# input.net
KiCad netlist of a schematic drawn in EAGLE
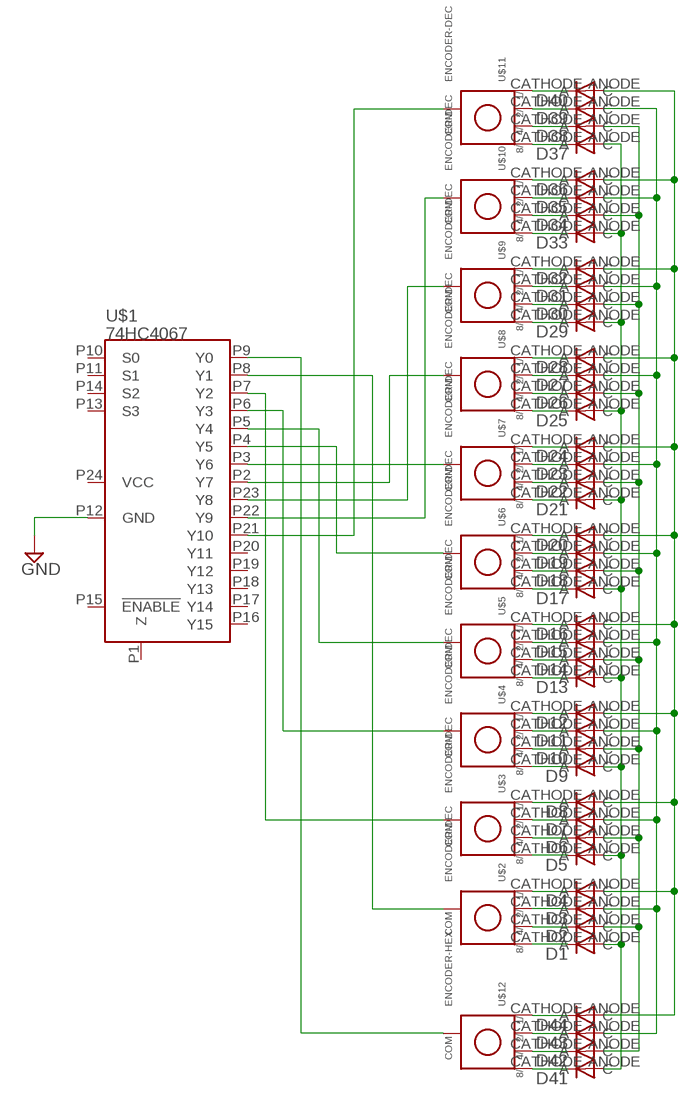
[diagram p0: schematic, sheet 1]

(export (version "E")
  (design (tool "Eeschema 10.0.6"))
  (components
    (comp (ref "D1")
      (value "TS4148")
      (footprint "eagle-import:0805")
      (libsource (lib "eagle-import") (part "TS4148"))
    )
    (comp (ref "D2")
      (value "TS4148")
      (footprint "eagle-import:0805")
      (libsource (lib "eagle-import") (part "TS4148"))
    )
    (comp (ref "D3")
      (value "TS4148")
      (footprint "eagle-import:0805")
      (libsource (lib "eagle-import") (part "TS4148"))
    )
    (comp (ref "D4")
      (value "TS4148")
      (footprint "eagle-import:0805")
      (libsource (lib "eagle-import") (part "TS4148"))
    )
    (comp (ref "D5")
      (value "TS4148")
      (footprint "eagle-import:0805")
      (libsource (lib "eagle-import") (part "TS4148"))
    )
    (comp (ref "D6")
      (value "TS4148")
      (footprint "eagle-import:0805")
      (libsource (lib "eagle-import") (part "TS4148"))
    )
    (comp (ref "D7")
      (value "TS4148")
      (footprint "eagle-import:0805")
      (libsource (lib "eagle-import") (part "TS4148"))
    )
    (comp (ref "D8")
      (value "TS4148")
      (footprint "eagle-import:0805")
      (libsource (lib "eagle-import") (part "TS4148"))
    )
    (comp (ref "D9")
      (value "TS4148")
      (footprint "eagle-import:0805")
      (libsource (lib "eagle-import") (part "TS4148"))
    )
    (comp (ref "D10")
      (value "TS4148")
      (footprint "eagle-import:0805")
      (libsource (lib "eagle-import") (part "TS4148"))
    )
    (comp (ref "D11")
      (value "TS4148")
      (footprint "eagle-import:0805")
      (libsource (lib "eagle-import") (part "TS4148"))
    )
    (comp (ref "D12")
      (value "TS4148")
      (footprint "eagle-import:0805")
      (libsource (lib "eagle-import") (part "TS4148"))
    )
    (comp (ref "D13")
      (value "TS4148")
      (footprint "eagle-import:0805")
      (libsource (lib "eagle-import") (part "TS4148"))
    )
    (comp (ref "D14")
      (value "TS4148")
      (footprint "eagle-import:0805")
      (libsource (lib "eagle-import") (part "TS4148"))
    )
    (comp (ref "D15")
      (value "TS4148")
      (footprint "eagle-import:0805")
      (libsource (lib "eagle-import") (part "TS4148"))
    )
    (comp (ref "D16")
      (value "TS4148")
      (footprint "eagle-import:0805")
      (libsource (lib "eagle-import") (part "TS4148"))
    )
    (comp (ref "D17")
      (value "TS4148")
      (footprint "eagle-import:0805")
      (libsource (lib "eagle-import") (part "TS4148"))
    )
    (comp (ref "D18")
      (value "TS4148")
      (footprint "eagle-import:0805")
      (libsource (lib "eagle-import") (part "TS4148"))
    )
    (comp (ref "D19")
      (value "TS4148")
      (footprint "eagle-import:0805")
      (libsource (lib "eagle-import") (part "TS4148"))
    )
    (comp (ref "D20")
      (value "TS4148")
      (footprint "eagle-import:0805")
      (libsource (lib "eagle-import") (part "TS4148"))
    )
    (comp (ref "D21")
      (value "TS4148")
      (footprint "eagle-import:0805")
      (libsource (lib "eagle-import") (part "TS4148"))
    )
    (comp (ref "D22")
      (value "TS4148")
      (footprint "eagle-import:0805")
      (libsource (lib "eagle-import") (part "TS4148"))
    )
    (comp (ref "D23")
      (value "TS4148")
      (footprint "eagle-import:0805")
      (libsource (lib "eagle-import") (part "TS4148"))
    )
    (comp (ref "D24")
      (value "TS4148")
      (footprint "eagle-import:0805")
      (libsource (lib "eagle-import") (part "TS4148"))
    )
    (comp (ref "D25")
      (value "TS4148")
      (footprint "eagle-import:0805")
      (libsource (lib "eagle-import") (part "TS4148"))
    )
    (comp (ref "D26")
      (value "TS4148")
      (footprint "eagle-import:0805")
      (libsource (lib "eagle-import") (part "TS4148"))
    )
    (comp (ref "D27")
      (value "TS4148")
      (footprint "eagle-import:0805")
      (libsource (lib "eagle-import") (part "TS4148"))
    )
    (comp (ref "D28")
      (value "TS4148")
      (footprint "eagle-import:0805")
      (libsource (lib "eagle-import") (part "TS4148"))
    )
    (comp (ref "D29")
      (value "TS4148")
      (footprint "eagle-import:0805")
      (libsource (lib "eagle-import") (part "TS4148"))
    )
    (comp (ref "D30")
      (value "TS4148")
      (footprint "eagle-import:0805")
      (libsource (lib "eagle-import") (part "TS4148"))
    )
    (comp (ref "D31")
      (value "TS4148")
      (footprint "eagle-import:0805")
      (libsource (lib "eagle-import") (part "TS4148"))
    )
    (comp (ref "D32")
      (value "TS4148")
      (footprint "eagle-import:0805")
      (libsource (lib "eagle-import") (part "TS4148"))
    )
    (comp (ref "D33")
      (value "TS4148")
      (footprint "eagle-import:0805")
      (libsource (lib "eagle-import") (part "TS4148"))
    )
    (comp (ref "D34")
      (value "TS4148")
      (footprint "eagle-import:0805")
      (libsource (lib "eagle-import") (part "TS4148"))
    )
    (comp (ref "D35")
      (value "TS4148")
      (footprint "eagle-import:0805")
      (libsource (lib "eagle-import") (part "TS4148"))
    )
    (comp (ref "D36")
      (value "TS4148")
      (footprint "eagle-import:0805")
      (libsource (lib "eagle-import") (part "TS4148"))
    )
    (comp (ref "D37")
      (value "TS4148")
      (footprint "eagle-import:0805")
      (libsource (lib "eagle-import") (part "TS4148"))
    )
    (comp (ref "D38")
      (value "TS4148")
      (footprint "eagle-import:0805")
      (libsource (lib "eagle-import") (part "TS4148"))
    )
    (comp (ref "D39")
      (value "TS4148")
      (footprint "eagle-import:0805")
      (libsource (lib "eagle-import") (part "TS4148"))
    )
    (comp (ref "D40")
      (value "TS4148")
      (footprint "eagle-import:0805")
      (libsource (lib "eagle-import") (part "TS4148"))
    )
    (comp (ref "D41")
      (value "TS4148")
      (footprint "eagle-import:0805")
      (libsource (lib "eagle-import") (part "TS4148"))
    )
    (comp (ref "D42")
      (value "TS4148")
      (footprint "eagle-import:0805")
      (libsource (lib "eagle-import") (part "TS4148"))
    )
    (comp (ref "D43")
      (value "TS4148")
      (footprint "eagle-import:0805")
      (libsource (lib "eagle-import") (part "TS4148"))
    )
    (comp (ref "D44")
      (value "TS4148")
      (footprint "eagle-import:0805")
      (libsource (lib "eagle-import") (part "TS4148"))
    )
    (comp (ref "U$1")
      (value "74HC4067")
      (footprint "eagle-import:DIP-24")
      (libsource (lib "eagle-import") (part "74HC4067"))
    )
    (comp (ref "U$2")
      (value "ENCODER-DEC")
      (footprint "eagle-import:4-BIT-ENCODER")
      (libsource (lib "eagle-import") (part "ENCODER-DEC"))
    )
    (comp (ref "U$3")
      (value "ENCODER-DEC")
      (footprint "eagle-import:4-BIT-ENCODER")
      (libsource (lib "eagle-import") (part "ENCODER-DEC"))
    )
    (comp (ref "U$4")
      (value "ENCODER-DEC")
      (footprint "eagle-import:4-BIT-ENCODER")
      (libsource (lib "eagle-import") (part "ENCODER-DEC"))
    )
    (comp (ref "U$5")
      (value "ENCODER-DEC")
      (footprint "eagle-import:4-BIT-ENCODER")
      (libsource (lib "eagle-import") (part "ENCODER-DEC"))
    )
    (comp (ref "U$6")
      (value "ENCODER-DEC")
      (footprint "eagle-import:4-BIT-ENCODER")
      (libsource (lib "eagle-import") (part "ENCODER-DEC"))
    )
    (comp (ref "U$7")
      (value "ENCODER-DEC")
      (footprint "eagle-import:4-BIT-ENCODER")
      (libsource (lib "eagle-import") (part "ENCODER-DEC"))
    )
    (comp (ref "U$8")
      (value "ENCODER-DEC")
      (footprint "eagle-import:4-BIT-ENCODER")
      (libsource (lib "eagle-import") (part "ENCODER-DEC"))
    )
    (comp (ref "U$9")
      (value "ENCODER-DEC")
      (footprint "eagle-import:4-BIT-ENCODER")
      (libsource (lib "eagle-import") (part "ENCODER-DEC"))
    )
    (comp (ref "U$10")
      (value "ENCODER-DEC")
      (footprint "eagle-import:4-BIT-ENCODER")
      (libsource (lib "eagle-import") (part "ENCODER-DEC"))
    )
    (comp (ref "U$11")
      (value "ENCODER-DEC")
      (footprint "eagle-import:4-BIT-ENCODER")
      (libsource (lib "eagle-import") (part "ENCODER-DEC"))
    )
    (comp (ref "U$12")
      (value "ENCODER-HEX")
      (footprint "eagle-import:4-BIT-ENCODER")
      (libsource (lib "eagle-import") (part "ENCODER-HEX"))
    )
  )
  (nets
    (net (code "1") (name "/VCC") (class "Default")
      (node (ref "U$1") (pin "P24") (pinfunction "VCC_P24") (pintype "power_in"))
    )
    (net (code "2") (name "GND") (class "Default")
      (node (ref "U$1") (pin "P12") (pinfunction "GND_P12") (pintype "power_in"))
    )
    (net (code "3") (name "Net-(D1-A)") (class "Default")
      (node (ref "D1") (pin "ANODE") (pinfunction "A_ANODE") (pintype "bidirectional"))
      (node (ref "D13") (pin "ANODE") (pinfunction "A_ANODE") (pintype "bidirectional"))
      (node (ref "D17") (pin "ANODE") (pinfunction "A_ANODE") (pintype "bidirectional"))
      (node (ref "D21") (pin "ANODE") (pinfunction "A_ANODE") (pintype "bidirectional"))
      (node (ref "D25") (pin "ANODE") (pinfunction "A_ANODE") (pintype "bidirectional"))
      (node (ref "D29") (pin "ANODE") (pinfunction "A_ANODE") (pintype "bidirectional"))
      (node (ref "D33") (pin "ANODE") (pinfunction "A_ANODE") (pintype "bidirectional"))
      (node (ref "D37") (pin "ANODE") (pinfunction "A_ANODE") (pintype "bidirectional"))
      (node (ref "D41") (pin "ANODE") (pinfunction "A_ANODE") (pintype "bidirectional"))
      (node (ref "D5") (pin "ANODE") (pinfunction "A_ANODE") (pintype "bidirectional"))
      (node (ref "D9") (pin "ANODE") (pinfunction "A_ANODE") (pintype "bidirectional"))
    )
    (net (code "4") (name "Net-(D1-C)") (class "Default")
      (node (ref "D1") (pin "CATHODE") (pinfunction "C_CATHODE") (pintype "bidirectional"))
      (node (ref "U$2") (pin "8/") (pinfunction "8/_8/") (pintype "bidirectional"))
    )
    (net (code "5") (name "Net-(D2-C)") (class "Default")
      (node (ref "D2") (pin "CATHODE") (pinfunction "C_CATHODE") (pintype "bidirectional"))
      (node (ref "U$2") (pin "4/") (pinfunction "4/_4/") (pintype "bidirectional"))
    )
    (net (code "6") (name "Net-(D3-C)") (class "Default")
      (node (ref "D3") (pin "CATHODE") (pinfunction "C_CATHODE") (pintype "bidirectional"))
      (node (ref "U$2") (pin "2/") (pinfunction "2/_2/") (pintype "bidirectional"))
    )
    (net (code "7") (name "Net-(D4-C)") (class "Default")
      (node (ref "D4") (pin "CATHODE") (pinfunction "C_CATHODE") (pintype "bidirectional"))
      (node (ref "U$2") (pin "1/") (pinfunction "1/_1/") (pintype "bidirectional"))
    )
    (net (code "8") (name "Net-(D5-C)") (class "Default")
      (node (ref "D5") (pin "CATHODE") (pinfunction "C_CATHODE") (pintype "bidirectional"))
      (node (ref "U$3") (pin "8/") (pinfunction "8/_8/") (pintype "bidirectional"))
    )
    (net (code "9") (name "Net-(D6-C)") (class "Default")
      (node (ref "D6") (pin "CATHODE") (pinfunction "C_CATHODE") (pintype "bidirectional"))
      (node (ref "U$3") (pin "4/") (pinfunction "4/_4/") (pintype "bidirectional"))
    )
    (net (code "10") (name "Net-(D7-C)") (class "Default")
      (node (ref "D7") (pin "CATHODE") (pinfunction "C_CATHODE") (pintype "bidirectional"))
      (node (ref "U$3") (pin "2/") (pinfunction "2/_2/") (pintype "bidirectional"))
    )
    (net (code "11") (name "Net-(D8-C)") (class "Default")
      (node (ref "D8") (pin "CATHODE") (pinfunction "C_CATHODE") (pintype "bidirectional"))
      (node (ref "U$3") (pin "1/") (pinfunction "1/_1/") (pintype "bidirectional"))
    )
    (net (code "12") (name "Net-(D9-C)") (class "Default")
      (node (ref "D9") (pin "CATHODE") (pinfunction "C_CATHODE") (pintype "bidirectional"))
      (node (ref "U$4") (pin "8/") (pinfunction "8/_8/") (pintype "bidirectional"))
    )
    (net (code "13") (name "Net-(D10-A)") (class "Default")
      (node (ref "D10") (pin "ANODE") (pinfunction "A_ANODE") (pintype "bidirectional"))
      (node (ref "D14") (pin "ANODE") (pinfunction "A_ANODE") (pintype "bidirectional"))
      (node (ref "D18") (pin "ANODE") (pinfunction "A_ANODE") (pintype "bidirectional"))
      (node (ref "D2") (pin "ANODE") (pinfunction "A_ANODE") (pintype "bidirectional"))
      (node (ref "D22") (pin "ANODE") (pinfunction "A_ANODE") (pintype "bidirectional"))
      (node (ref "D26") (pin "ANODE") (pinfunction "A_ANODE") (pintype "bidirectional"))
      (node (ref "D30") (pin "ANODE") (pinfunction "A_ANODE") (pintype "bidirectional"))
      (node (ref "D34") (pin "ANODE") (pinfunction "A_ANODE") (pintype "bidirectional"))
      (node (ref "D38") (pin "ANODE") (pinfunction "A_ANODE") (pintype "bidirectional"))
      (node (ref "D42") (pin "ANODE") (pinfunction "A_ANODE") (pintype "bidirectional"))
      (node (ref "D6") (pin "ANODE") (pinfunction "A_ANODE") (pintype "bidirectional"))
    )
    (net (code "14") (name "Net-(D10-C)") (class "Default")
      (node (ref "D10") (pin "CATHODE") (pinfunction "C_CATHODE") (pintype "bidirectional"))
      (node (ref "U$4") (pin "4/") (pinfunction "4/_4/") (pintype "bidirectional"))
    )
    (net (code "15") (name "Net-(D11-A)") (class "Default")
      (node (ref "D11") (pin "ANODE") (pinfunction "A_ANODE") (pintype "bidirectional"))
      (node (ref "D15") (pin "ANODE") (pinfunction "A_ANODE") (pintype "bidirectional"))
      (node (ref "D19") (pin "ANODE") (pinfunction "A_ANODE") (pintype "bidirectional"))
      (node (ref "D23") (pin "ANODE") (pinfunction "A_ANODE") (pintype "bidirectional"))
      (node (ref "D27") (pin "ANODE") (pinfunction "A_ANODE") (pintype "bidirectional"))
      (node (ref "D3") (pin "ANODE") (pinfunction "A_ANODE") (pintype "bidirectional"))
      (node (ref "D31") (pin "ANODE") (pinfunction "A_ANODE") (pintype "bidirectional"))
      (node (ref "D35") (pin "ANODE") (pinfunction "A_ANODE") (pintype "bidirectional"))
      (node (ref "D39") (pin "ANODE") (pinfunction "A_ANODE") (pintype "bidirectional"))
      (node (ref "D43") (pin "ANODE") (pinfunction "A_ANODE") (pintype "bidirectional"))
      (node (ref "D7") (pin "ANODE") (pinfunction "A_ANODE") (pintype "bidirectional"))
    )
    (net (code "16") (name "Net-(D11-C)") (class "Default")
      (node (ref "D11") (pin "CATHODE") (pinfunction "C_CATHODE") (pintype "bidirectional"))
      (node (ref "U$4") (pin "2/") (pinfunction "2/_2/") (pintype "bidirectional"))
    )
    (net (code "17") (name "Net-(D12-A)") (class "Default")
      (node (ref "D12") (pin "ANODE") (pinfunction "A_ANODE") (pintype "bidirectional"))
      (node (ref "D16") (pin "ANODE") (pinfunction "A_ANODE") (pintype "bidirectional"))
      (node (ref "D20") (pin "ANODE") (pinfunction "A_ANODE") (pintype "bidirectional"))
      (node (ref "D24") (pin "ANODE") (pinfunction "A_ANODE") (pintype "bidirectional"))
      (node (ref "D28") (pin "ANODE") (pinfunction "A_ANODE") (pintype "bidirectional"))
      (node (ref "D32") (pin "ANODE") (pinfunction "A_ANODE") (pintype "bidirectional"))
      (node (ref "D36") (pin "ANODE") (pinfunction "A_ANODE") (pintype "bidirectional"))
      (node (ref "D4") (pin "ANODE") (pinfunction "A_ANODE") (pintype "bidirectional"))
      (node (ref "D40") (pin "ANODE") (pinfunction "A_ANODE") (pintype "bidirectional"))
      (node (ref "D44") (pin "ANODE") (pinfunction "A_ANODE") (pintype "bidirectional"))
      (node (ref "D8") (pin "ANODE") (pinfunction "A_ANODE") (pintype "bidirectional"))
    )
    (net (code "18") (name "Net-(D12-C)") (class "Default")
      (node (ref "D12") (pin "CATHODE") (pinfunction "C_CATHODE") (pintype "bidirectional"))
      (node (ref "U$4") (pin "1/") (pinfunction "1/_1/") (pintype "bidirectional"))
    )
    (net (code "19") (name "Net-(D13-C)") (class "Default")
      (node (ref "D13") (pin "CATHODE") (pinfunction "C_CATHODE") (pintype "bidirectional"))
      (node (ref "U$5") (pin "8/") (pinfunction "8/_8/") (pintype "bidirectional"))
    )
    (net (code "20") (name "Net-(D14-C)") (class "Default")
      (node (ref "D14") (pin "CATHODE") (pinfunction "C_CATHODE") (pintype "bidirectional"))
      (node (ref "U$5") (pin "4/") (pinfunction "4/_4/") (pintype "bidirectional"))
    )
    (net (code "21") (name "Net-(D15-C)") (class "Default")
      (node (ref "D15") (pin "CATHODE") (pinfunction "C_CATHODE") (pintype "bidirectional"))
      (node (ref "U$5") (pin "2/") (pinfunction "2/_2/") (pintype "bidirectional"))
    )
    (net (code "22") (name "Net-(D16-C)") (class "Default")
      (node (ref "D16") (pin "CATHODE") (pinfunction "C_CATHODE") (pintype "bidirectional"))
      (node (ref "U$5") (pin "1/") (pinfunction "1/_1/") (pintype "bidirectional"))
    )
    (net (code "23") (name "Net-(D17-C)") (class "Default")
      (node (ref "D17") (pin "CATHODE") (pinfunction "C_CATHODE") (pintype "bidirectional"))
      (node (ref "U$6") (pin "8/") (pinfunction "8/_8/") (pintype "bidirectional"))
    )
    (net (code "24") (name "Net-(D18-C)") (class "Default")
      (node (ref "D18") (pin "CATHODE") (pinfunction "C_CATHODE") (pintype "bidirectional"))
      (node (ref "U$6") (pin "4/") (pinfunction "4/_4/") (pintype "bidirectional"))
    )
    (net (code "25") (name "Net-(D19-C)") (class "Default")
      (node (ref "D19") (pin "CATHODE") (pinfunction "C_CATHODE") (pintype "bidirectional"))
      (node (ref "U$6") (pin "2/") (pinfunction "2/_2/") (pintype "bidirectional"))
    )
    (net (code "26") (name "Net-(D20-C)") (class "Default")
      (node (ref "D20") (pin "CATHODE") (pinfunction "C_CATHODE") (pintype "bidirectional"))
      (node (ref "U$6") (pin "1/") (pinfunction "1/_1/") (pintype "bidirectional"))
    )
    (net (code "27") (name "Net-(D21-C)") (class "Default")
      (node (ref "D21") (pin "CATHODE") (pinfunction "C_CATHODE") (pintype "bidirectional"))
      (node (ref "U$7") (pin "8/") (pinfunction "8/_8/") (pintype "bidirectional"))
    )
    (net (code "28") (name "Net-(D22-C)") (class "Default")
      (node (ref "D22") (pin "CATHODE") (pinfunction "C_CATHODE") (pintype "bidirectional"))
      (node (ref "U$7") (pin "4/") (pinfunction "4/_4/") (pintype "bidirectional"))
    )
    (net (code "29") (name "Net-(D23-C)") (class "Default")
      (node (ref "D23") (pin "CATHODE") (pinfunction "C_CATHODE") (pintype "bidirectional"))
      (node (ref "U$7") (pin "2/") (pinfunction "2/_2/") (pintype "bidirectional"))
    )
    (net (code "30") (name "Net-(D24-C)") (class "Default")
      (node (ref "D24") (pin "CATHODE") (pinfunction "C_CATHODE") (pintype "bidirectional"))
      (node (ref "U$7") (pin "1/") (pinfunction "1/_1/") (pintype "bidirectional"))
    )
    (net (code "31") (name "Net-(D25-C)") (class "Default")
      (node (ref "D25") (pin "CATHODE") (pinfunction "C_CATHODE") (pintype "bidirectional"))
      (node (ref "U$8") (pin "8/") (pinfunction "8/_8/") (pintype "bidirectional"))
    )
    (net (code "32") (name "Net-(D26-C)") (class "Default")
      (node (ref "D26") (pin "CATHODE") (pinfunction "C_CATHODE") (pintype "bidirectional"))
      (node (ref "U$8") (pin "4/") (pinfunction "4/_4/") (pintype "bidirectional"))
    )
    (net (code "33") (name "Net-(D27-C)") (class "Default")
      (node (ref "D27") (pin "CATHODE") (pinfunction "C_CATHODE") (pintype "bidirectional"))
      (node (ref "U$8") (pin "2/") (pinfunction "2/_2/") (pintype "bidirectional"))
    )
    (net (code "34") (name "Net-(D28-C)") (class "Default")
      (node (ref "D28") (pin "CATHODE") (pinfunction "C_CATHODE") (pintype "bidirectional"))
      (node (ref "U$8") (pin "1/") (pinfunction "1/_1/") (pintype "bidirectional"))
    )
    (net (code "35") (name "Net-(D29-C)") (class "Default")
      (node (ref "D29") (pin "CATHODE") (pinfunction "C_CATHODE") (pintype "bidirectional"))
      (node (ref "U$9") (pin "8/") (pinfunction "8/_8/") (pintype "bidirectional"))
    )
    (net (code "36") (name "Net-(D30-C)") (class "Default")
      (node (ref "D30") (pin "CATHODE") (pinfunction "C_CATHODE") (pintype "bidirectional"))
      (node (ref "U$9") (pin "4/") (pinfunction "4/_4/") (pintype "bidirectional"))
    )
    (net (code "37") (name "Net-(D31-C)") (class "Default")
      (node (ref "D31") (pin "CATHODE") (pinfunction "C_CATHODE") (pintype "bidirectional"))
      (node (ref "U$9") (pin "2/") (pinfunction "2/_2/") (pintype "bidirectional"))
    )
    (net (code "38") (name "Net-(D32-C)") (class "Default")
      (node (ref "D32") (pin "CATHODE") (pinfunction "C_CATHODE") (pintype "bidirectional"))
      (node (ref "U$9") (pin "1/") (pinfunction "1/_1/") (pintype "bidirectional"))
    )
    (net (code "39") (name "Net-(D33-C)") (class "Default")
      (node (ref "D33") (pin "CATHODE") (pinfunction "C_CATHODE") (pintype "bidirectional"))
      (node (ref "U$10") (pin "8/") (pinfunction "8/_8/") (pintype "bidirectional"))
    )
    (net (code "40") (name "Net-(D34-C)") (class "Default")
      (node (ref "D34") (pin "CATHODE") (pinfunction "C_CATHODE") (pintype "bidirectional"))
      (node (ref "U$10") (pin "4/") (pinfunction "4/_4/") (pintype "bidirectional"))
    )
    (net (code "41") (name "Net-(D35-C)") (class "Default")
      (node (ref "D35") (pin "CATHODE") (pinfunction "C_CATHODE") (pintype "bidirectional"))
      (node (ref "U$10") (pin "2/") (pinfunction "2/_2/") (pintype "bidirectional"))
    )
    (net (code "42") (name "Net-(D36-C)") (class "Default")
      (node (ref "D36") (pin "CATHODE") (pinfunction "C_CATHODE") (pintype "bidirectional"))
      (node (ref "U$10") (pin "1/") (pinfunction "1/_1/") (pintype "bidirectional"))
    )
    (net (code "43") (name "Net-(D37-C)") (class "Default")
      (node (ref "D37") (pin "CATHODE") (pinfunction "C_CATHODE") (pintype "bidirectional"))
      (node (ref "U$11") (pin "8/") (pinfunction "8/_8/") (pintype "bidirectional"))
    )
    (net (code "44") (name "Net-(D38-C)") (class "Default")
      (node (ref "D38") (pin "CATHODE") (pinfunction "C_CATHODE") (pintype "bidirectional"))
      (node (ref "U$11") (pin "4/") (pinfunction "4/_4/") (pintype "bidirectional"))
    )
    (net (code "45") (name "Net-(D39-C)") (class "Default")
      (node (ref "D39") (pin "CATHODE") (pinfunction "C_CATHODE") (pintype "bidirectional"))
      (node (ref "U$11") (pin "2/") (pinfunction "2/_2/") (pintype "bidirectional"))
    )
    (net (code "46") (name "Net-(D40-C)") (class "Default")
      (node (ref "D40") (pin "CATHODE") (pinfunction "C_CATHODE") (pintype "bidirectional"))
      (node (ref "U$11") (pin "1/") (pinfunction "1/_1/") (pintype "bidirectional"))
    )
    (net (code "47") (name "Net-(D41-C)") (class "Default")
      (node (ref "D41") (pin "CATHODE") (pinfunction "C_CATHODE") (pintype "bidirectional"))
      (node (ref "U$12") (pin "8/") (pinfunction "8/_8/") (pintype "bidirectional"))
    )
    (net (code "48") (name "Net-(D42-C)") (class "Default")
      (node (ref "D42") (pin "CATHODE") (pinfunction "C_CATHODE") (pintype "bidirectional"))
      (node (ref "U$12") (pin "4/") (pinfunction "4/_4/") (pintype "bidirectional"))
    )
    (net (code "49") (name "Net-(D43-C)") (class "Default")
      (node (ref "D43") (pin "CATHODE") (pinfunction "C_CATHODE") (pintype "bidirectional"))
      (node (ref "U$12") (pin "2/") (pinfunction "2/_2/") (pintype "bidirectional"))
    )
    (net (code "50") (name "Net-(D44-C)") (class "Default")
      (node (ref "D44") (pin "CATHODE") (pinfunction "C_CATHODE") (pintype "bidirectional"))
      (node (ref "U$12") (pin "1/") (pinfunction "1/_1/") (pintype "bidirectional"))
    )
    (net (code "51") (name "Net-(U$1-Y0)") (class "Default")
      (node (ref "U$1") (pin "P9") (pinfunction "Y0_P9") (pintype "bidirectional"))
      (node (ref "U$12") (pin "COMMON") (pinfunction "COMMON_COMMON") (pintype "bidirectional"))
    )
    (net (code "52") (name "Net-(U$1-Y1)") (class "Default")
      (node (ref "U$1") (pin "P8") (pinfunction "Y1_P8") (pintype "bidirectional"))
      (node (ref "U$2") (pin "COMMON") (pinfunction "COMMON_COMMON") (pintype "bidirectional"))
    )
    (net (code "53") (name "Net-(U$1-Y2)") (class "Default")
      (node (ref "U$1") (pin "P7") (pinfunction "Y2_P7") (pintype "bidirectional"))
      (node (ref "U$3") (pin "COMMON") (pinfunction "COMMON_COMMON") (pintype "bidirectional"))
    )
    (net (code "54") (name "Net-(U$1-Y3)") (class "Default")
      (node (ref "U$1") (pin "P6") (pinfunction "Y3_P6") (pintype "bidirectional"))
      (node (ref "U$4") (pin "COMMON") (pinfunction "COMMON_COMMON") (pintype "bidirectional"))
    )
    (net (code "55") (name "Net-(U$1-Y4)") (class "Default")
      (node (ref "U$1") (pin "P5") (pinfunction "Y4_P5") (pintype "bidirectional"))
      (node (ref "U$5") (pin "COMMON") (pinfunction "COMMON_COMMON") (pintype "bidirectional"))
    )
    (net (code "56") (name "Net-(U$1-Y5)") (class "Default")
      (node (ref "U$1") (pin "P4") (pinfunction "Y5_P4") (pintype "bidirectional"))
      (node (ref "U$6") (pin "COMMON") (pinfunction "COMMON_COMMON") (pintype "bidirectional"))
    )
    (net (code "57") (name "Net-(U$1-Y6)") (class "Default")
      (node (ref "U$1") (pin "P3") (pinfunction "Y6_P3") (pintype "bidirectional"))
      (node (ref "U$7") (pin "COMMON") (pinfunction "COMMON_COMMON") (pintype "bidirectional"))
    )
    (net (code "58") (name "Net-(U$1-Y7)") (class "Default")
      (node (ref "U$1") (pin "P2") (pinfunction "Y7_P2") (pintype "bidirectional"))
      (node (ref "U$8") (pin "COMMON") (pinfunction "COMMON_COMMON") (pintype "bidirectional"))
    )
    (net (code "59") (name "Net-(U$1-Y8)") (class "Default")
      (node (ref "U$1") (pin "P23") (pinfunction "Y8_P23") (pintype "bidirectional"))
      (node (ref "U$9") (pin "COMMON") (pinfunction "COMMON_COMMON") (pintype "bidirectional"))
    )
    (net (code "60") (name "Net-(U$1-Y9)") (class "Default")
      (node (ref "U$1") (pin "P22") (pinfunction "Y9_P22") (pintype "bidirectional"))
      (node (ref "U$10") (pin "COMMON") (pinfunction "COMMON_COMMON") (pintype "bidirectional"))
    )
    (net (code "61") (name "Net-(U$1-Y10)") (class "Default")
      (node (ref "U$1") (pin "P21") (pinfunction "Y10_P21") (pintype "bidirectional"))
      (node (ref "U$11") (pin "COMMON") (pinfunction "COMMON_COMMON") (pintype "bidirectional"))
    )
    (net (code "62") (name "unconnected-(U$1-S0-PadP10)") (class "Default")
      (node (ref "U$1") (pin "P10") (pinfunction "S0_P10") (pintype "bidirectional"))
    )
    (net (code "63") (name "unconnected-(U$1-S1-PadP11)") (class "Default")
      (node (ref "U$1") (pin "P11") (pinfunction "S1_P11") (pintype "bidirectional"))
    )
    (net (code "64") (name "unconnected-(U$1-S2-PadP14)") (class "Default")
      (node (ref "U$1") (pin "P14") (pinfunction "S2_P14") (pintype "bidirectional"))
    )
    (net (code "65") (name "unconnected-(U$1-S3-PadP13)") (class "Default")
      (node (ref "U$1") (pin "P13") (pinfunction "S3_P13") (pintype "bidirectional"))
    )
    (net (code "66") (name "unconnected-(U$1-Y11-PadP20)") (class "Default")
      (node (ref "U$1") (pin "P20") (pinfunction "Y11_P20") (pintype "bidirectional"))
    )
    (net (code "67") (name "unconnected-(U$1-Y12-PadP19)") (class "Default")
      (node (ref "U$1") (pin "P19") (pinfunction "Y12_P19") (pintype "bidirectional"))
    )
    (net (code "68") (name "unconnected-(U$1-Y13-PadP18)") (class "Default")
      (node (ref "U$1") (pin "P18") (pinfunction "Y13_P18") (pintype "bidirectional"))
    )
    (net (code "69") (name "unconnected-(U$1-Y14-PadP17)") (class "Default")
      (node (ref "U$1") (pin "P17") (pinfunction "Y14_P17") (pintype "bidirectional"))
    )
    (net (code "70") (name "unconnected-(U$1-Y15-PadP16)") (class "Default")
      (node (ref "U$1") (pin "P16") (pinfunction "Y15_P16") (pintype "bidirectional"))
    )
    (net (code "71") (name "unconnected-(U$1-Z-PadP1)") (class "Default")
      (node (ref "U$1") (pin "P1") (pinfunction "Z_P1") (pintype "bidirectional"))
    )
    (net (code "72") (name "unconnected-(U$1-~{ENABLE}-PadP15)") (class "Default")
      (node (ref "U$1") (pin "P15") (pinfunction "~{ENABLE}_P15") (pintype "bidirectional"))
    )
  )
)
